# Pololu_Magnetic_Encoder_Floating_AS5035.net
KiCad netlist of a schematic drawn in EAGLE
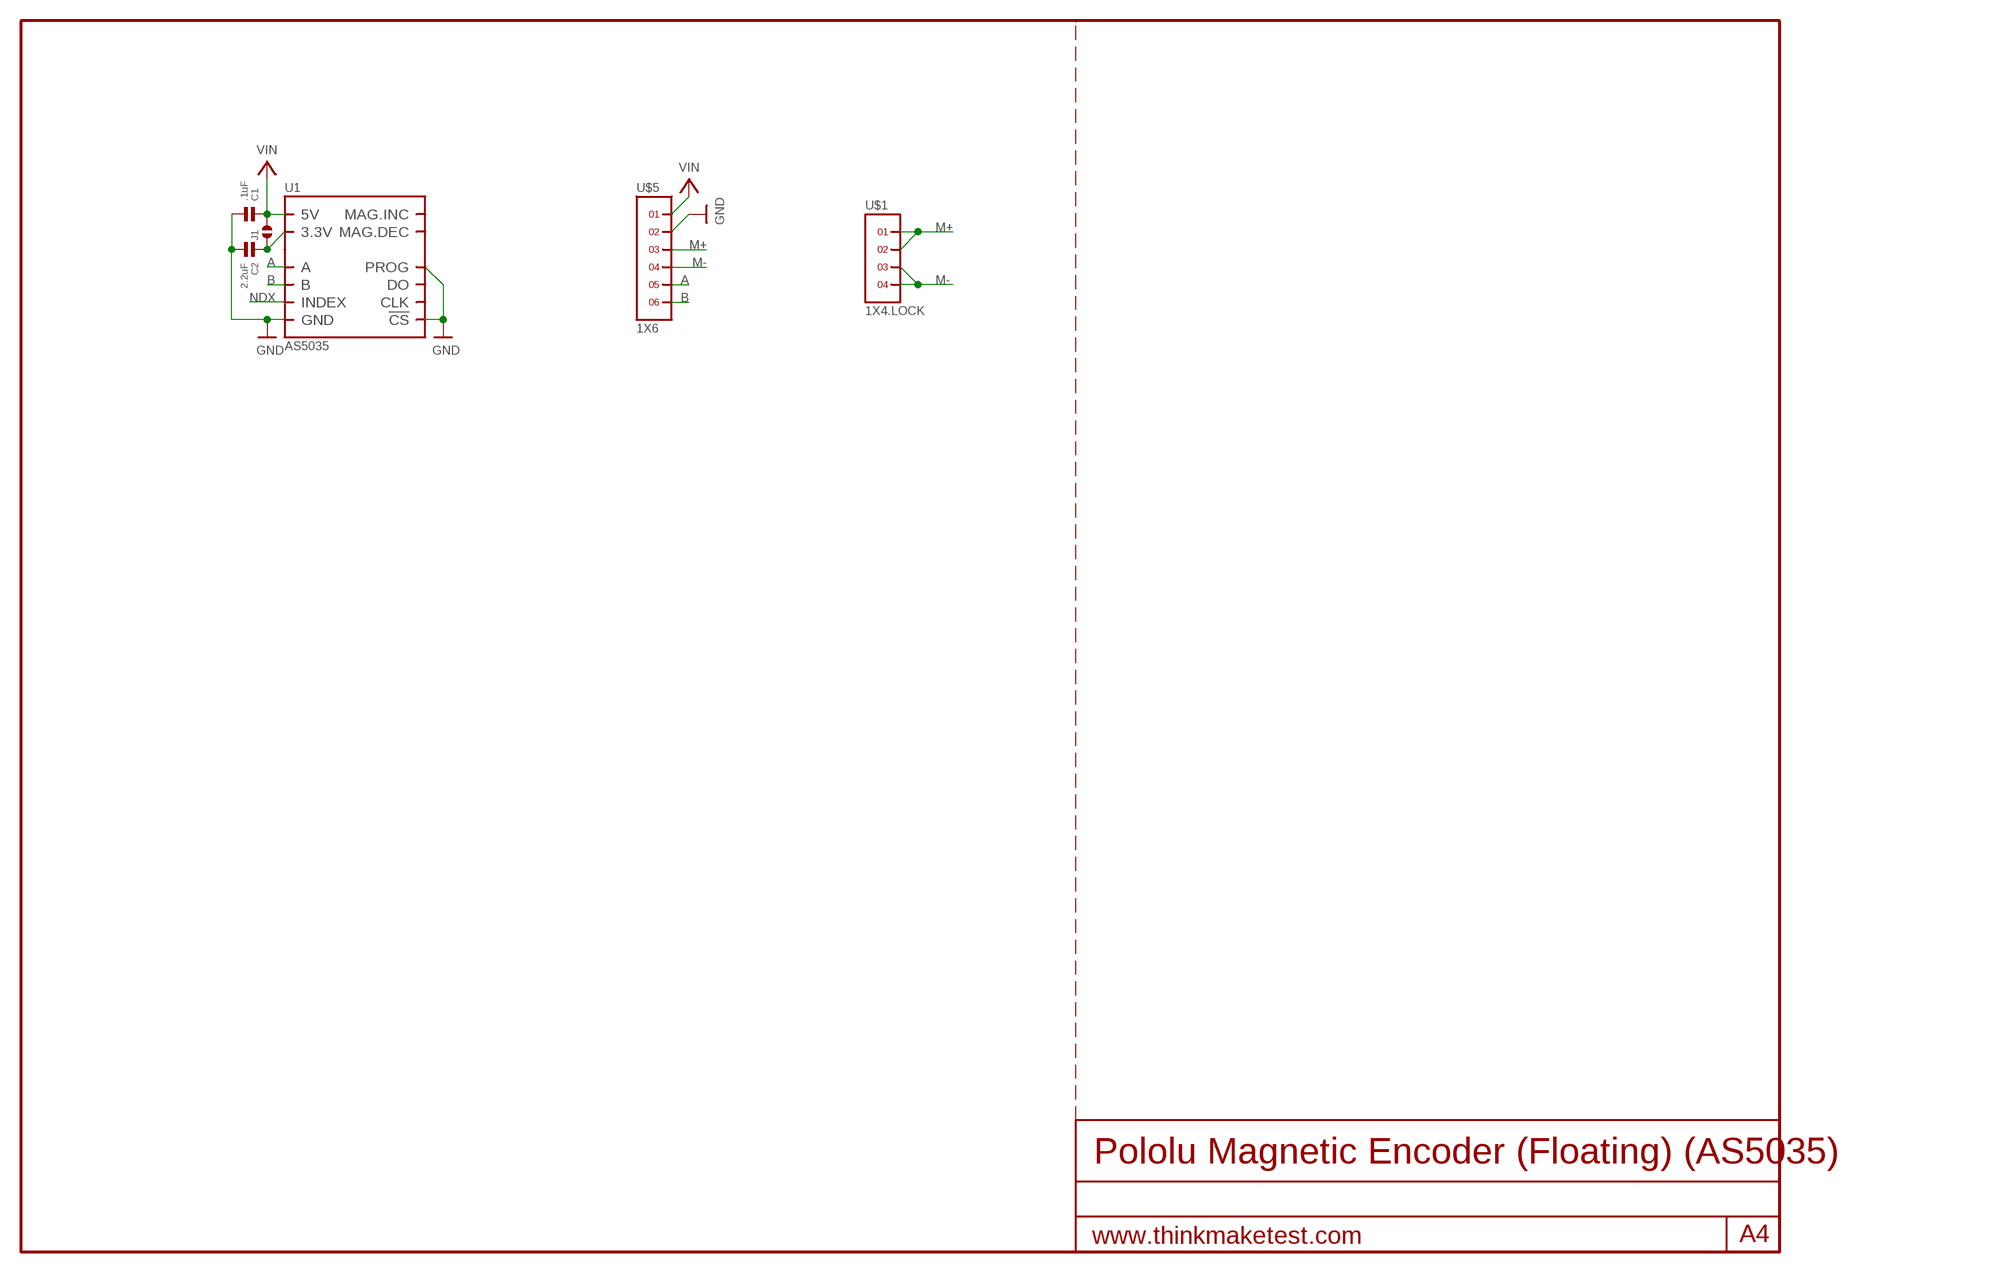
[diagram p0: schematic, sheet 1]

(export (version "E")
  (design (tool "Eeschema 10.0.6"))
  (components
    (comp (ref "C1")
      (value ".1uF")
      (footprint "eagle-import:0603")
      (libsource (lib "eagle-import") (part "CAPACITOR.0603"))
    )
    (comp (ref "C2")
      (value "2.2uF")
      (footprint "eagle-import:0603")
      (libsource (lib "eagle-import") (part "CAPACITOR.0603"))
    )
    (comp (ref "J1")
      (value "SOLDERJUMPER.2.LRG.PASTE")
      (footprint "eagle-import:2.LRG.PASTE")
      (libsource (lib "eagle-import") (part "SOLDERJUMPER.2.LRG.PASTE"))
    )
    (comp (ref "U$1")
      (value "1X4.LOCK")
      (footprint "eagle-import:1X4.LOCK")
      (libsource (lib "eagle-import") (part "1X4.LOCK"))
    )
    (comp (ref "U$5")
      (value "1X6")
      (footprint "eagle-import:1X6")
      (libsource (lib "eagle-import") (part "1X6"))
    )
    (comp (ref "U1")
      (value "AS5035")
      (footprint "eagle-import:SSOP16")
      (libsource (lib "eagle-import") (part "AS5035"))
    )
  )
  (nets
    (net (code "1") (name "/A") (class "Default")
      (node (ref "U$5") (pin "5") (pinfunction "5_5") (pintype "bidirectional"))
      (node (ref "U1") (pin "3") (pinfunction "A_3") (pintype "bidirectional"))
    )
    (net (code "2") (name "/B") (class "Default")
      (node (ref "U$5") (pin "6") (pinfunction "6_6") (pintype "bidirectional"))
      (node (ref "U1") (pin "4") (pinfunction "B_4") (pintype "bidirectional"))
    )
    (net (code "3") (name "/M+") (class "Default")
      (node (ref "U$1") (pin "1") (pinfunction "1_1") (pintype "bidirectional"))
      (node (ref "U$1") (pin "2") (pinfunction "2_2") (pintype "bidirectional"))
      (node (ref "U$5") (pin "3") (pinfunction "3_3") (pintype "bidirectional"))
    )
    (net (code "4") (name "/M-") (class "Default")
      (node (ref "U$1") (pin "3") (pinfunction "3_3") (pintype "bidirectional"))
      (node (ref "U$1") (pin "4") (pinfunction "4_4") (pintype "bidirectional"))
      (node (ref "U$5") (pin "4") (pinfunction "4_4") (pintype "bidirectional"))
    )
    (net (code "5") (name "/NDX") (class "Default")
      (node (ref "U1") (pin "6") (pinfunction "INDEX_6") (pintype "bidirectional"))
    )
    (net (code "6") (name "GND") (class "Default")
      (node (ref "C1") (pin "2") (pinfunction "2_2") (pintype "bidirectional"))
      (node (ref "C2") (pin "2") (pinfunction "2_2") (pintype "bidirectional"))
      (node (ref "U$5") (pin "2") (pinfunction "2_2") (pintype "bidirectional"))
      (node (ref "U1") (pin "11") (pinfunction "~{CS}_11") (pintype "bidirectional"))
      (node (ref "U1") (pin "7") (pinfunction "GND_7") (pintype "bidirectional"))
      (node (ref "U1") (pin "8") (pinfunction "PROG_8") (pintype "bidirectional"))
    )
    (net (code "7") (name "Net-(U1-3.3V)") (class "Default")
      (node (ref "C2") (pin "1") (pinfunction "1_1") (pintype "bidirectional"))
      (node (ref "J1") (pin "1") (pinfunction "1_1") (pintype "bidirectional"))
      (node (ref "U1") (pin "15") (pinfunction "3.3V_15") (pintype "bidirectional"))
    )
    (net (code "8") (name "VIN") (class "Default")
      (node (ref "C1") (pin "1") (pinfunction "1_1") (pintype "bidirectional"))
      (node (ref "J1") (pin "2") (pinfunction "2_2") (pintype "bidirectional"))
      (node (ref "U$5") (pin "1") (pinfunction "1_1") (pintype "bidirectional"))
      (node (ref "U1") (pin "16") (pinfunction "5V_16") (pintype "bidirectional"))
    )
    (net (code "9") (name "unconnected-(U1-CLK-Pad10)") (class "Default")
      (node (ref "U1") (pin "10") (pinfunction "CLK_10") (pintype "bidirectional"))
    )
    (net (code "10") (name "unconnected-(U1-DO-Pad9)") (class "Default")
      (node (ref "U1") (pin "9") (pinfunction "DO_9") (pintype "bidirectional"))
    )
    (net (code "11") (name "unconnected-(U1-MAG.DEC-Pad2)") (class "Default")
      (node (ref "U1") (pin "2") (pinfunction "MAG.DEC_2") (pintype "bidirectional"))
    )
    (net (code "12") (name "unconnected-(U1-MAG.INC-Pad1)") (class "Default")
      (node (ref "U1") (pin "1") (pinfunction "MAG.INC_1") (pintype "bidirectional"))
    )
  )
)
